# untitled.net
KiCad netlist of a schematic drawn in EAGLE
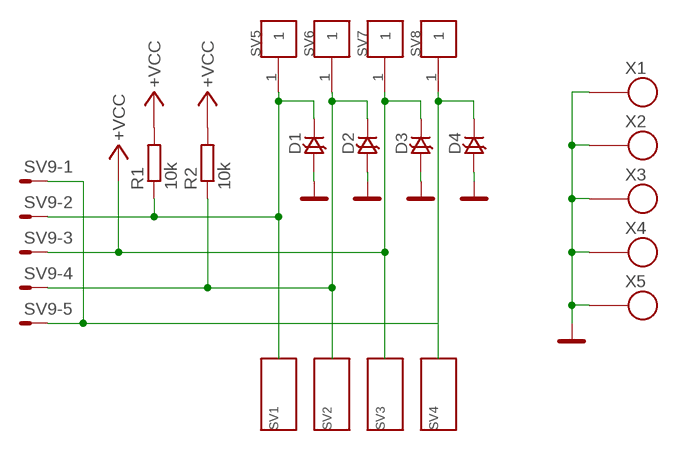
[diagram p0: schematic, sheet 1]

(export (version "E")
  (design (tool "Eeschema 10.0.6"))
  (components
    (comp (ref "D1")
      (value "D-TRANSIL-SMA")
      (footprint "eagle-import:SMA")
      (libsource (lib "eagle-import") (part "D-TRANSIL-SMA"))
    )
    (comp (ref "D2")
      (value "D-TRANSIL-SMA")
      (footprint "eagle-import:SMA")
      (libsource (lib "eagle-import") (part "D-TRANSIL-SMA"))
    )
    (comp (ref "D3")
      (value "D-TRANSIL-SMA")
      (footprint "eagle-import:SMA")
      (libsource (lib "eagle-import") (part "D-TRANSIL-SMA"))
    )
    (comp (ref "D4")
      (value "D-TRANSIL-SMA")
      (footprint "eagle-import:SMA")
      (libsource (lib "eagle-import") (part "D-TRANSIL-SMA"))
    )
    (comp (ref "R1")
      (value "10k")
      (footprint "eagle-import:0805")
      (libsource (lib "eagle-import") (part "R0805"))
    )
    (comp (ref "R2")
      (value "10k")
      (footprint "eagle-import:0805")
      (libsource (lib "eagle-import") (part "R0805"))
    )
    (comp (ref "SV1")
      (value "WAGO256")
      (footprint "eagle-import:WAGO256")
      (libsource (lib "eagle-import") (part "WAGO256"))
    )
    (comp (ref "SV2")
      (value "WAGO256")
      (footprint "eagle-import:WAGO256")
      (libsource (lib "eagle-import") (part "WAGO256"))
    )
    (comp (ref "SV3")
      (value "WAGO256")
      (footprint "eagle-import:WAGO256")
      (libsource (lib "eagle-import") (part "WAGO256"))
    )
    (comp (ref "SV4")
      (value "WAGO256")
      (footprint "eagle-import:WAGO256")
      (libsource (lib "eagle-import") (part "WAGO256"))
    )
    (comp (ref "SV5")
      (value "SMD:MA01-01")
      (footprint "eagle-import:SMD_MA01-1")
      (libsource (lib "eagle-import") (part "SMD{colon}MA01-01"))
    )
    (comp (ref "SV6")
      (value "SMD:MA01-01")
      (footprint "eagle-import:SMD_MA01-1")
      (libsource (lib "eagle-import") (part "SMD{colon}MA01-01"))
    )
    (comp (ref "SV7")
      (value "SMD:MA01-01")
      (footprint "eagle-import:SMD_MA01-1")
      (libsource (lib "eagle-import") (part "SMD{colon}MA01-01"))
    )
    (comp (ref "SV8")
      (value "SMD:MA01-01")
      (footprint "eagle-import:SMD_MA01-1")
      (libsource (lib "eagle-import") (part "SMD{colon}MA01-01"))
    )
    (comp (ref "SV9")
      (value "MA05-1")
      (footprint "eagle-import:MA05-1")
      (libsource (lib "eagle-import") (part "MA05-1"))
    )
    (comp (ref "X1")
      (value "SROUB3M")
      (footprint "eagle-import:SROUB3M")
      (libsource (lib "eagle-import") (part "SROUB3M"))
    )
    (comp (ref "X2")
      (value "SROUB3M")
      (footprint "eagle-import:SROUB3M")
      (libsource (lib "eagle-import") (part "SROUB3M"))
    )
    (comp (ref "X3")
      (value "SROUB3M")
      (footprint "eagle-import:SROUB3M")
      (libsource (lib "eagle-import") (part "SROUB3M"))
    )
    (comp (ref "X4")
      (value "SROUB3M")
      (footprint "eagle-import:SROUB3M")
      (libsource (lib "eagle-import") (part "SROUB3M"))
    )
    (comp (ref "X5")
      (value "SROUB3M")
      (footprint "eagle-import:SROUB3M")
      (libsource (lib "eagle-import") (part "SROUB3M"))
    )
  )
  (nets
    (net (code "1") (name "+VCC") (class "Default")
      (node (ref "D3") (pin "K") (pinfunction "K_K") (pintype "passive"))
      (node (ref "R1") (pin "2") (pinfunction "2_2") (pintype "passive"))
      (node (ref "R2") (pin "2") (pinfunction "2_2") (pintype "passive"))
      (node (ref "SV3") (pin "1") (pinfunction "P$1_1") (pintype "passive"))
      (node (ref "SV3") (pin "A1") (pinfunction "P$1_A1") (pintype "passive"))
      (node (ref "SV7") (pin "1") (pinfunction "1_1") (pintype "bidirectional"))
      (node (ref "SV9") (pin "3") (pinfunction "P$1_3") (pintype "passive"))
    )
    (net (code "2") (name "GND") (class "Default")
      (node (ref "D1") (pin "A") (pinfunction "A_A") (pintype "passive"))
      (node (ref "D2") (pin "A") (pinfunction "A_A") (pintype "passive"))
      (node (ref "D3") (pin "A") (pinfunction "A_A") (pintype "passive"))
      (node (ref "D4") (pin "A") (pinfunction "A_A") (pintype "passive"))
      (node (ref "X1") (pin "P$1") (pinfunction "P$1_P$1") (pintype "bidirectional"))
      (node (ref "X2") (pin "P$1") (pinfunction "P$1_P$1") (pintype "bidirectional"))
      (node (ref "X3") (pin "P$1") (pinfunction "P$1_P$1") (pintype "bidirectional"))
      (node (ref "X4") (pin "P$1") (pinfunction "P$1_P$1") (pintype "bidirectional"))
      (node (ref "X5") (pin "P$1") (pinfunction "P$1_P$1") (pintype "bidirectional"))
    )
    (net (code "3") (name "Net-(SV9A-P$1)") (class "Default")
      (node (ref "D4") (pin "K") (pinfunction "K_K") (pintype "passive"))
      (node (ref "SV4") (pin "1") (pinfunction "P$1_1") (pintype "passive"))
      (node (ref "SV4") (pin "A1") (pinfunction "P$1_A1") (pintype "passive"))
      (node (ref "SV8") (pin "1") (pinfunction "1_1") (pintype "bidirectional"))
      (node (ref "SV9") (pin "1") (pinfunction "P$1_1") (pintype "passive"))
      (node (ref "SV9") (pin "5") (pinfunction "P$1_5") (pintype "passive"))
    )
    (net (code "4") (name "Net-(SV9B-P$1)") (class "Default")
      (node (ref "D1") (pin "K") (pinfunction "K_K") (pintype "passive"))
      (node (ref "R1") (pin "1") (pinfunction "1_1") (pintype "passive"))
      (node (ref "SV1") (pin "1") (pinfunction "P$1_1") (pintype "passive"))
      (node (ref "SV1") (pin "A1") (pinfunction "P$1_A1") (pintype "passive"))
      (node (ref "SV5") (pin "1") (pinfunction "1_1") (pintype "bidirectional"))
      (node (ref "SV9") (pin "2") (pinfunction "P$1_2") (pintype "passive"))
    )
    (net (code "5") (name "Net-(SV9D-P$1)") (class "Default")
      (node (ref "D2") (pin "K") (pinfunction "K_K") (pintype "passive"))
      (node (ref "R2") (pin "1") (pinfunction "1_1") (pintype "passive"))
      (node (ref "SV2") (pin "1") (pinfunction "P$1_1") (pintype "passive"))
      (node (ref "SV2") (pin "A1") (pinfunction "P$1_A1") (pintype "passive"))
      (node (ref "SV6") (pin "1") (pinfunction "1_1") (pintype "bidirectional"))
      (node (ref "SV9") (pin "4") (pinfunction "P$1_4") (pintype "passive"))
    )
  )
)
